# IoT_Greenhouse_V1_0_A_-_Inputs.net
KiCad netlist of a schematic drawn in Altium Designer
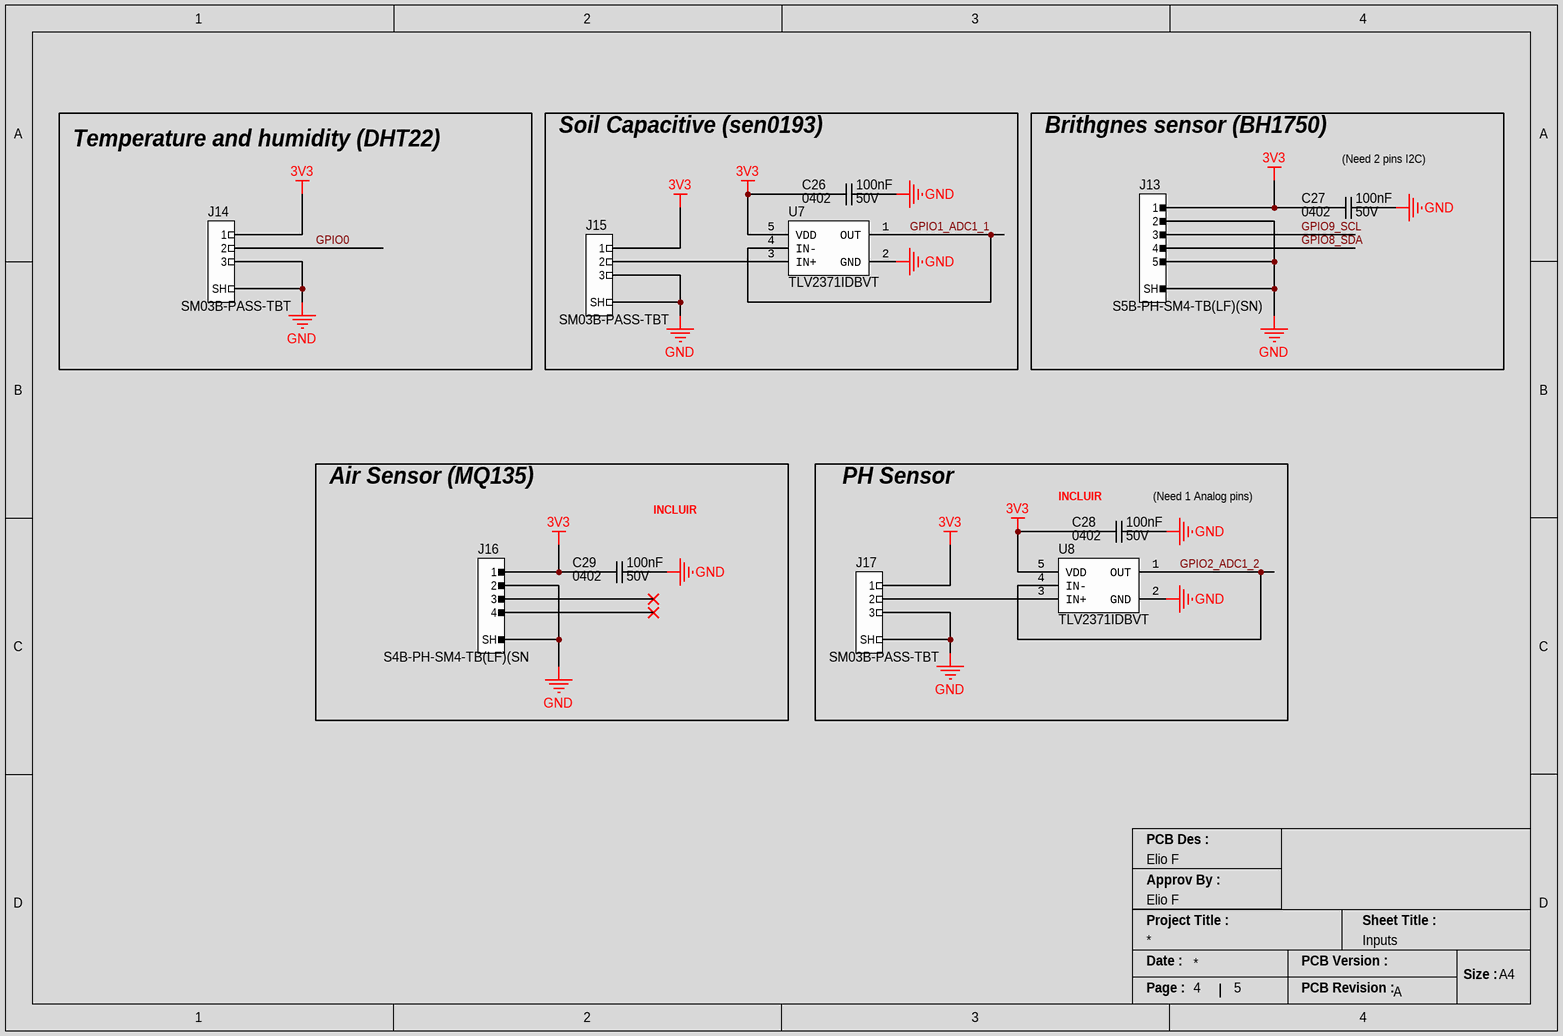
[diagram p0: IoT_Greenhouse V1.0 A - Inputs.SchDoc]

(export (version "E")
  (design (tool "Eeschema 10.0.6"))
  (components
    (comp (ref "C26")
      (value "GRM155R71H104KE14D")
      (footprint "CAP_0402_CAPC1005X05N")
      (description "Multilayer Ceramic Capacitor, 0.1 uF, 16 V, ± 10%, X7R, 0402 [1005 Metric]")
      (fields
        (field (name "MANUFACTURER") "Murata")
        (field (name "TOLERANCE") "10%")
        (field (name "VOLTAGE RATING") "50V")
        (field (name "CAPACITANCE") "100nF")
        (field (name "CASE/PACKAGE") "0402")
      )
      (libsource (lib "Electronic Devices_LIB") (part "CAP_100NF_50V_X7R_0402"))
    )
    (comp (ref "C27")
      (value "GRM155R71H104KE14D")
      (footprint "CAP_0402_CAPC1005X05N")
      (description "Multilayer Ceramic Capacitor, 0.1 uF, 16 V, ± 10%, X7R, 0402 [1005 Metric]")
      (fields
        (field (name "MANUFACTURER") "Murata")
        (field (name "TOLERANCE") "10%")
        (field (name "VOLTAGE RATING") "50V")
        (field (name "CAPACITANCE") "100nF")
        (field (name "CASE/PACKAGE") "0402")
      )
      (libsource (lib "Electronic Devices_LIB") (part "CAP_100NF_50V_X7R_0402"))
    )
    (comp (ref "C28")
      (value "GRM155R71H104KE14D")
      (footprint "CAP_0402_CAPC1005X05N")
      (description "Multilayer Ceramic Capacitor, 0.1 uF, 16 V, ± 10%, X7R, 0402 [1005 Metric]")
      (fields
        (field (name "MANUFACTURER") "Murata")
        (field (name "TOLERANCE") "10%")
        (field (name "VOLTAGE RATING") "50V")
        (field (name "CAPACITANCE") "100nF")
        (field (name "CASE/PACKAGE") "0402")
      )
      (libsource (lib "Electronic Devices_LIB") (part "CAP_100NF_50V_X7R_0402"))
    )
    (comp (ref "C29")
      (value "GRM155R71H104KE14D")
      (footprint "CAP_0402_CAPC1005X05N")
      (description "Multilayer Ceramic Capacitor, 0.1 uF, 16 V, ± 10%, X7R, 0402 [1005 Metric]")
      (fields
        (field (name "MANUFACTURER") "Murata")
        (field (name "TOLERANCE") "10%")
        (field (name "VOLTAGE RATING") "50V")
        (field (name "CAPACITANCE") "100nF")
        (field (name "CASE/PACKAGE") "0402")
      )
      (libsource (lib "Electronic Devices_LIB") (part "CAP_100NF_50V_X7R_0402"))
    )
    (comp (ref "J13")
      (value "S5B-PH-SM4-TB(LF)(SN)")
      (footprint "CONN_JST_S5B-PH-SM4-TB_LF_SN_0")
      (description "Conn Shrouded Header (4 Sides) HDR 5 POS 2mm Solder RA SMD T/R")
      (fields (field (name "MANUFACTURER") "JST"))
      (libsource (lib "Electronic Devices_LIB") (part "CONN_JST_PH_RA_5P_2mm"))
    )
    (comp (ref "J14")
      (value "SM03B-PASS-TBT")
      (footprint "CONN_JST_SM03B-PASS-TBT_LF_SN_MFG")
      (description "Conn Header SMD R/a 3POS 2MM")
      (fields (field (name "MANUFACTURER") "JST"))
      (libsource (lib "Electronic Devices_LIB") (part "CONN_JST_PH_3P_2MM_SM03B-PASS-TBT"))
    )
    (comp (ref "J15")
      (value "SM03B-PASS-TBT")
      (footprint "CONN_JST_SM03B-PASS-TBT_LF_SN_MFG")
      (description "Conn Header SMD R/a 3POS 2MM")
      (fields (field (name "MANUFACTURER") "JST"))
      (libsource (lib "Electronic Devices_LIB") (part "CONN_JST_PH_3P_2MM_SM03B-PASS-TBT"))
    )
    (comp (ref "J16")
      (value "S4B-PH-SM4-TB(LF)(SN")
      (footprint "CONN_JST_S4B-PH-SM4-TB_LF_SN_0")
      (fields (field (name "MANUFACTURER") "JST") (field (name "JLCPCB PART NUMBER") "C265102"))
      (libsource (lib "Electronic Devices_LIB") (part "CONN_JST_PH_RA_4P_2mm_JLCPCB"))
    )
    (comp (ref "J17")
      (value "SM03B-PASS-TBT")
      (footprint "CONN_JST_SM03B-PASS-TBT_LF_SN_MFG")
      (description "Conn Header SMD R/a 3POS 2MM")
      (fields (field (name "MANUFACTURER") "JST"))
      (libsource (lib "Electronic Devices_LIB") (part "CONN_JST_PH_3P_2MM_SM03B-PASS-TBT"))
    )
    (comp (ref "U7")
      (value "TLV2371IDBVT")
      (footprint "IC_AMP_OP_SOT95P280X145-5N")
      (description "Single 550-uA/channel, 3MHz, RRIO op amp 5-SOT-23 -40 to 125")
      (fields (field (name "MANUFACTURER") "Texas Instruments"))
      (libsource (lib "Electronic Devices_LIB") (part "IC_AMP_OP_TLV2371IDBVT"))
    )
    (comp (ref "U8")
      (value "TLV2371IDBVT")
      (footprint "IC_AMP_OP_SOT95P280X145-5N")
      (description "Single 550-uA/channel, 3MHz, RRIO op amp 5-SOT-23 -40 to 125")
      (fields (field (name "MANUFACTURER") "Texas Instruments"))
      (libsource (lib "Electronic Devices_LIB") (part "IC_AMP_OP_TLV2371IDBVT"))
    )
  )
  (nets
    (net (code "1") (name "/GPIO0") (class "Default")
      (node (ref "J14") (pin "2") (pinfunction "2_2") (pintype "passive"))
    )
    (net (code "2") (name "/GPIO1_ADC1_1") (class "Default")
      (node (ref "U7") (pin "1") (pinfunction "OUT_1") (pintype "passive"))
      (node (ref "U7") (pin "4") (pinfunction "IN-_4") (pintype "passive"))
    )
    (net (code "3") (name "/GPIO2_ADC1_2") (class "Default")
      (node (ref "U8") (pin "1") (pinfunction "OUT_1") (pintype "passive"))
      (node (ref "U8") (pin "4") (pinfunction "IN-_4") (pintype "passive"))
    )
    (net (code "4") (name "/GPIO8_SDA") (class "Default")
      (node (ref "J13") (pin "4") (pinfunction "4_4") (pintype "passive"))
    )
    (net (code "5") (name "/GPIO9_SCL") (class "Default")
      (node (ref "J13") (pin "3") (pinfunction "3_3") (pintype "passive"))
    )
    (net (code "6") (name "3V3") (class "Default")
      (node (ref "C26") (pin "2") (pinfunction "2_2") (pintype "passive"))
      (node (ref "C27") (pin "2") (pinfunction "2_2") (pintype "passive"))
      (node (ref "C28") (pin "2") (pinfunction "2_2") (pintype "passive"))
      (node (ref "C29") (pin "2") (pinfunction "2_2") (pintype "passive"))
      (node (ref "J13") (pin "1") (pinfunction "1_1") (pintype "passive"))
      (node (ref "J14") (pin "1") (pinfunction "1_1") (pintype "passive"))
      (node (ref "J15") (pin "1") (pinfunction "1_1") (pintype "passive"))
      (node (ref "J16") (pin "1") (pinfunction "1_1") (pintype "passive"))
      (node (ref "J17") (pin "1") (pinfunction "1_1") (pintype "passive"))
      (node (ref "U7") (pin "5") (pinfunction "VDD_5") (pintype "power_in"))
      (node (ref "U8") (pin "5") (pinfunction "VDD_5") (pintype "power_in"))
    )
    (net (code "7") (name "GND") (class "Default")
      (node (ref "C26") (pin "1") (pinfunction "1_1") (pintype "passive"))
      (node (ref "C27") (pin "1") (pinfunction "1_1") (pintype "passive"))
      (node (ref "C28") (pin "1") (pinfunction "1_1") (pintype "passive"))
      (node (ref "C29") (pin "1") (pinfunction "1_1") (pintype "passive"))
      (node (ref "J13") (pin "0") (pinfunction "SH_0") (pintype "passive"))
      (node (ref "J13") (pin "2") (pinfunction "2_2") (pintype "passive"))
      (node (ref "J13") (pin "5") (pinfunction "5_5") (pintype "passive"))
      (node (ref "J14") (pin "3") (pinfunction "3_3") (pintype "passive"))
      (node (ref "J14") (pin "SH") (pinfunction "SH_SH") (pintype "passive"))
      (node (ref "J15") (pin "3") (pinfunction "3_3") (pintype "passive"))
      (node (ref "J15") (pin "SH") (pinfunction "SH_SH") (pintype "passive"))
      (node (ref "J16") (pin "0") (pinfunction "SH_0") (pintype "passive"))
      (node (ref "J16") (pin "2") (pinfunction "2_2") (pintype "passive"))
      (node (ref "J17") (pin "3") (pinfunction "3_3") (pintype "passive"))
      (node (ref "J17") (pin "SH") (pinfunction "SH_SH") (pintype "passive"))
      (node (ref "U7") (pin "2") (pinfunction "GND_2") (pintype "power_in"))
      (node (ref "U8") (pin "2") (pinfunction "GND_2") (pintype "power_in"))
    )
    (net (code "8") (name "Net-(U7-IN+)") (class "Default")
      (node (ref "J15") (pin "2") (pinfunction "2_2") (pintype "passive"))
      (node (ref "U7") (pin "3") (pinfunction "IN+_3") (pintype "passive"))
    )
    (net (code "9") (name "Net-(U8-IN+)") (class "Default")
      (node (ref "J17") (pin "2") (pinfunction "2_2") (pintype "passive"))
      (node (ref "U8") (pin "3") (pinfunction "IN+_3") (pintype "passive"))
    )
    (net (code "10") (name "unconnected-(J16-Pad3)") (class "Default")
      (node (ref "J16") (pin "3") (pinfunction "3_3") (pintype "passive+no_connect"))
    )
    (net (code "11") (name "unconnected-(J16-Pad4)") (class "Default")
      (node (ref "J16") (pin "4") (pinfunction "4_4") (pintype "passive+no_connect"))
    )
  )
)
